# EthToRS485_V1_AUTO.net
KiCad netlist of a schematic drawn in EAGLE
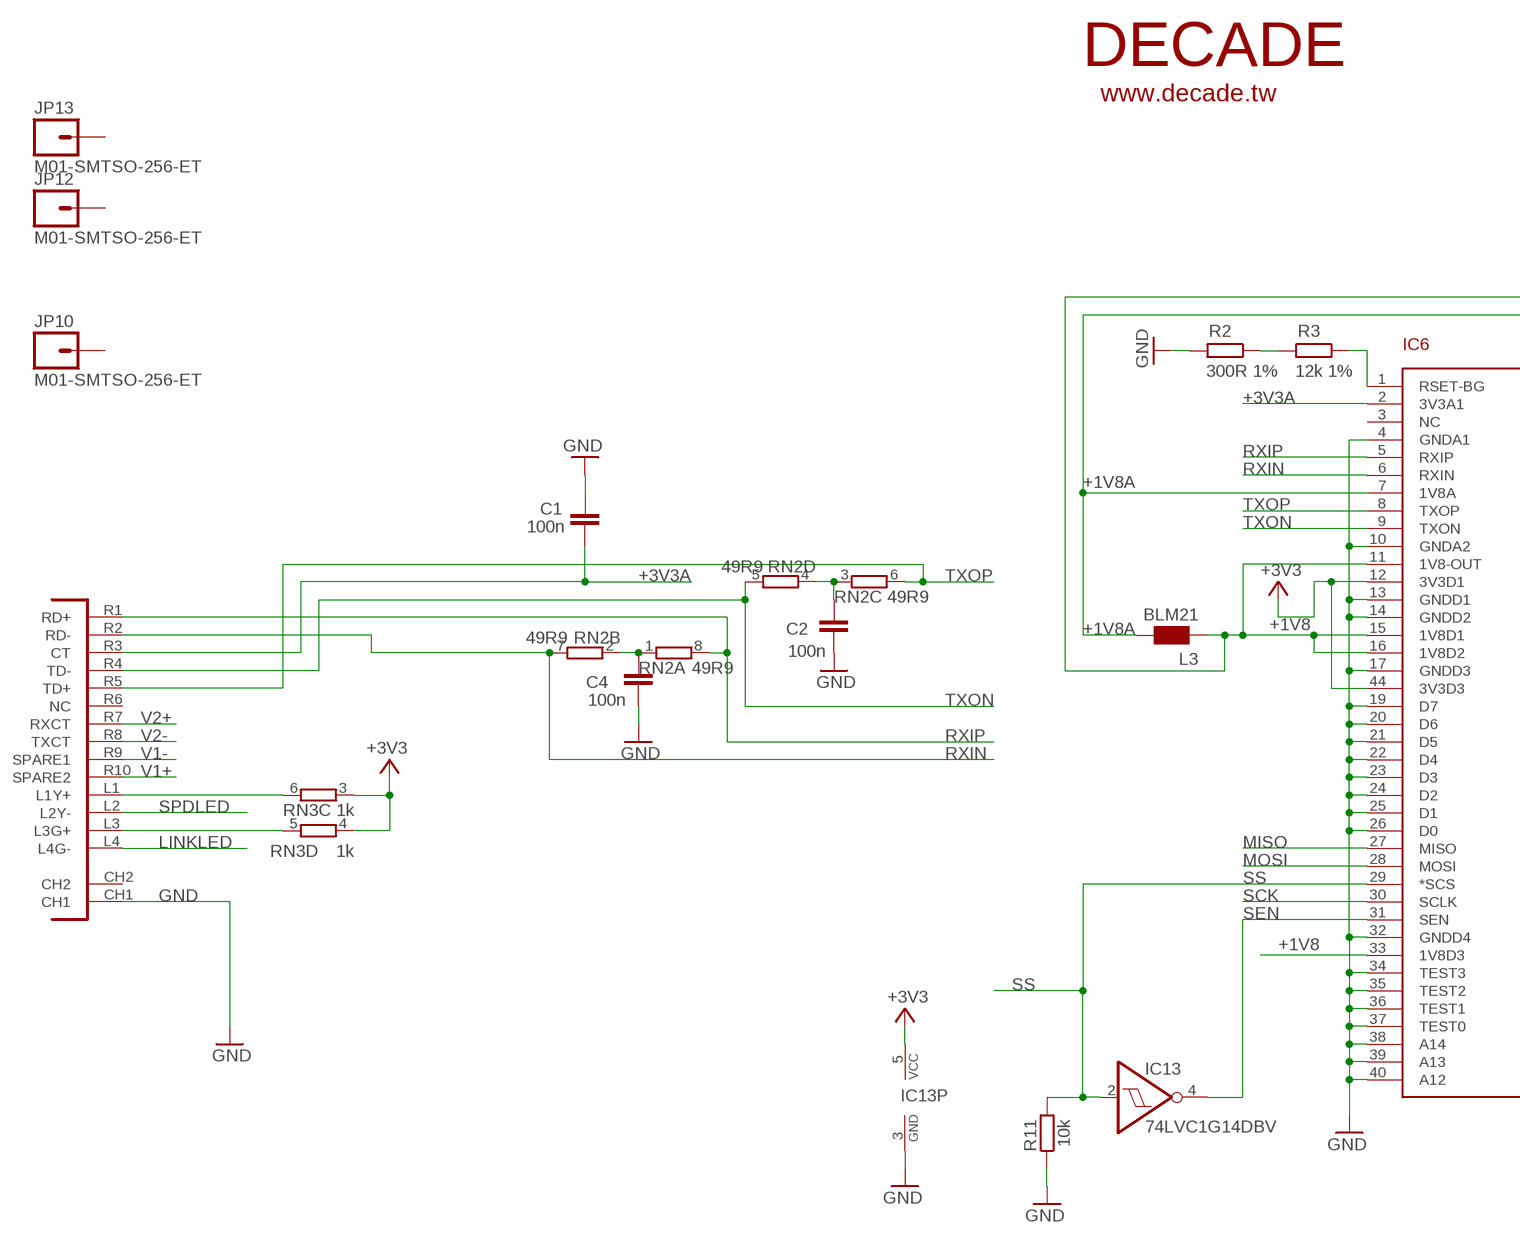
[diagram p0: schematic, sheet 1, part 1 of 3]
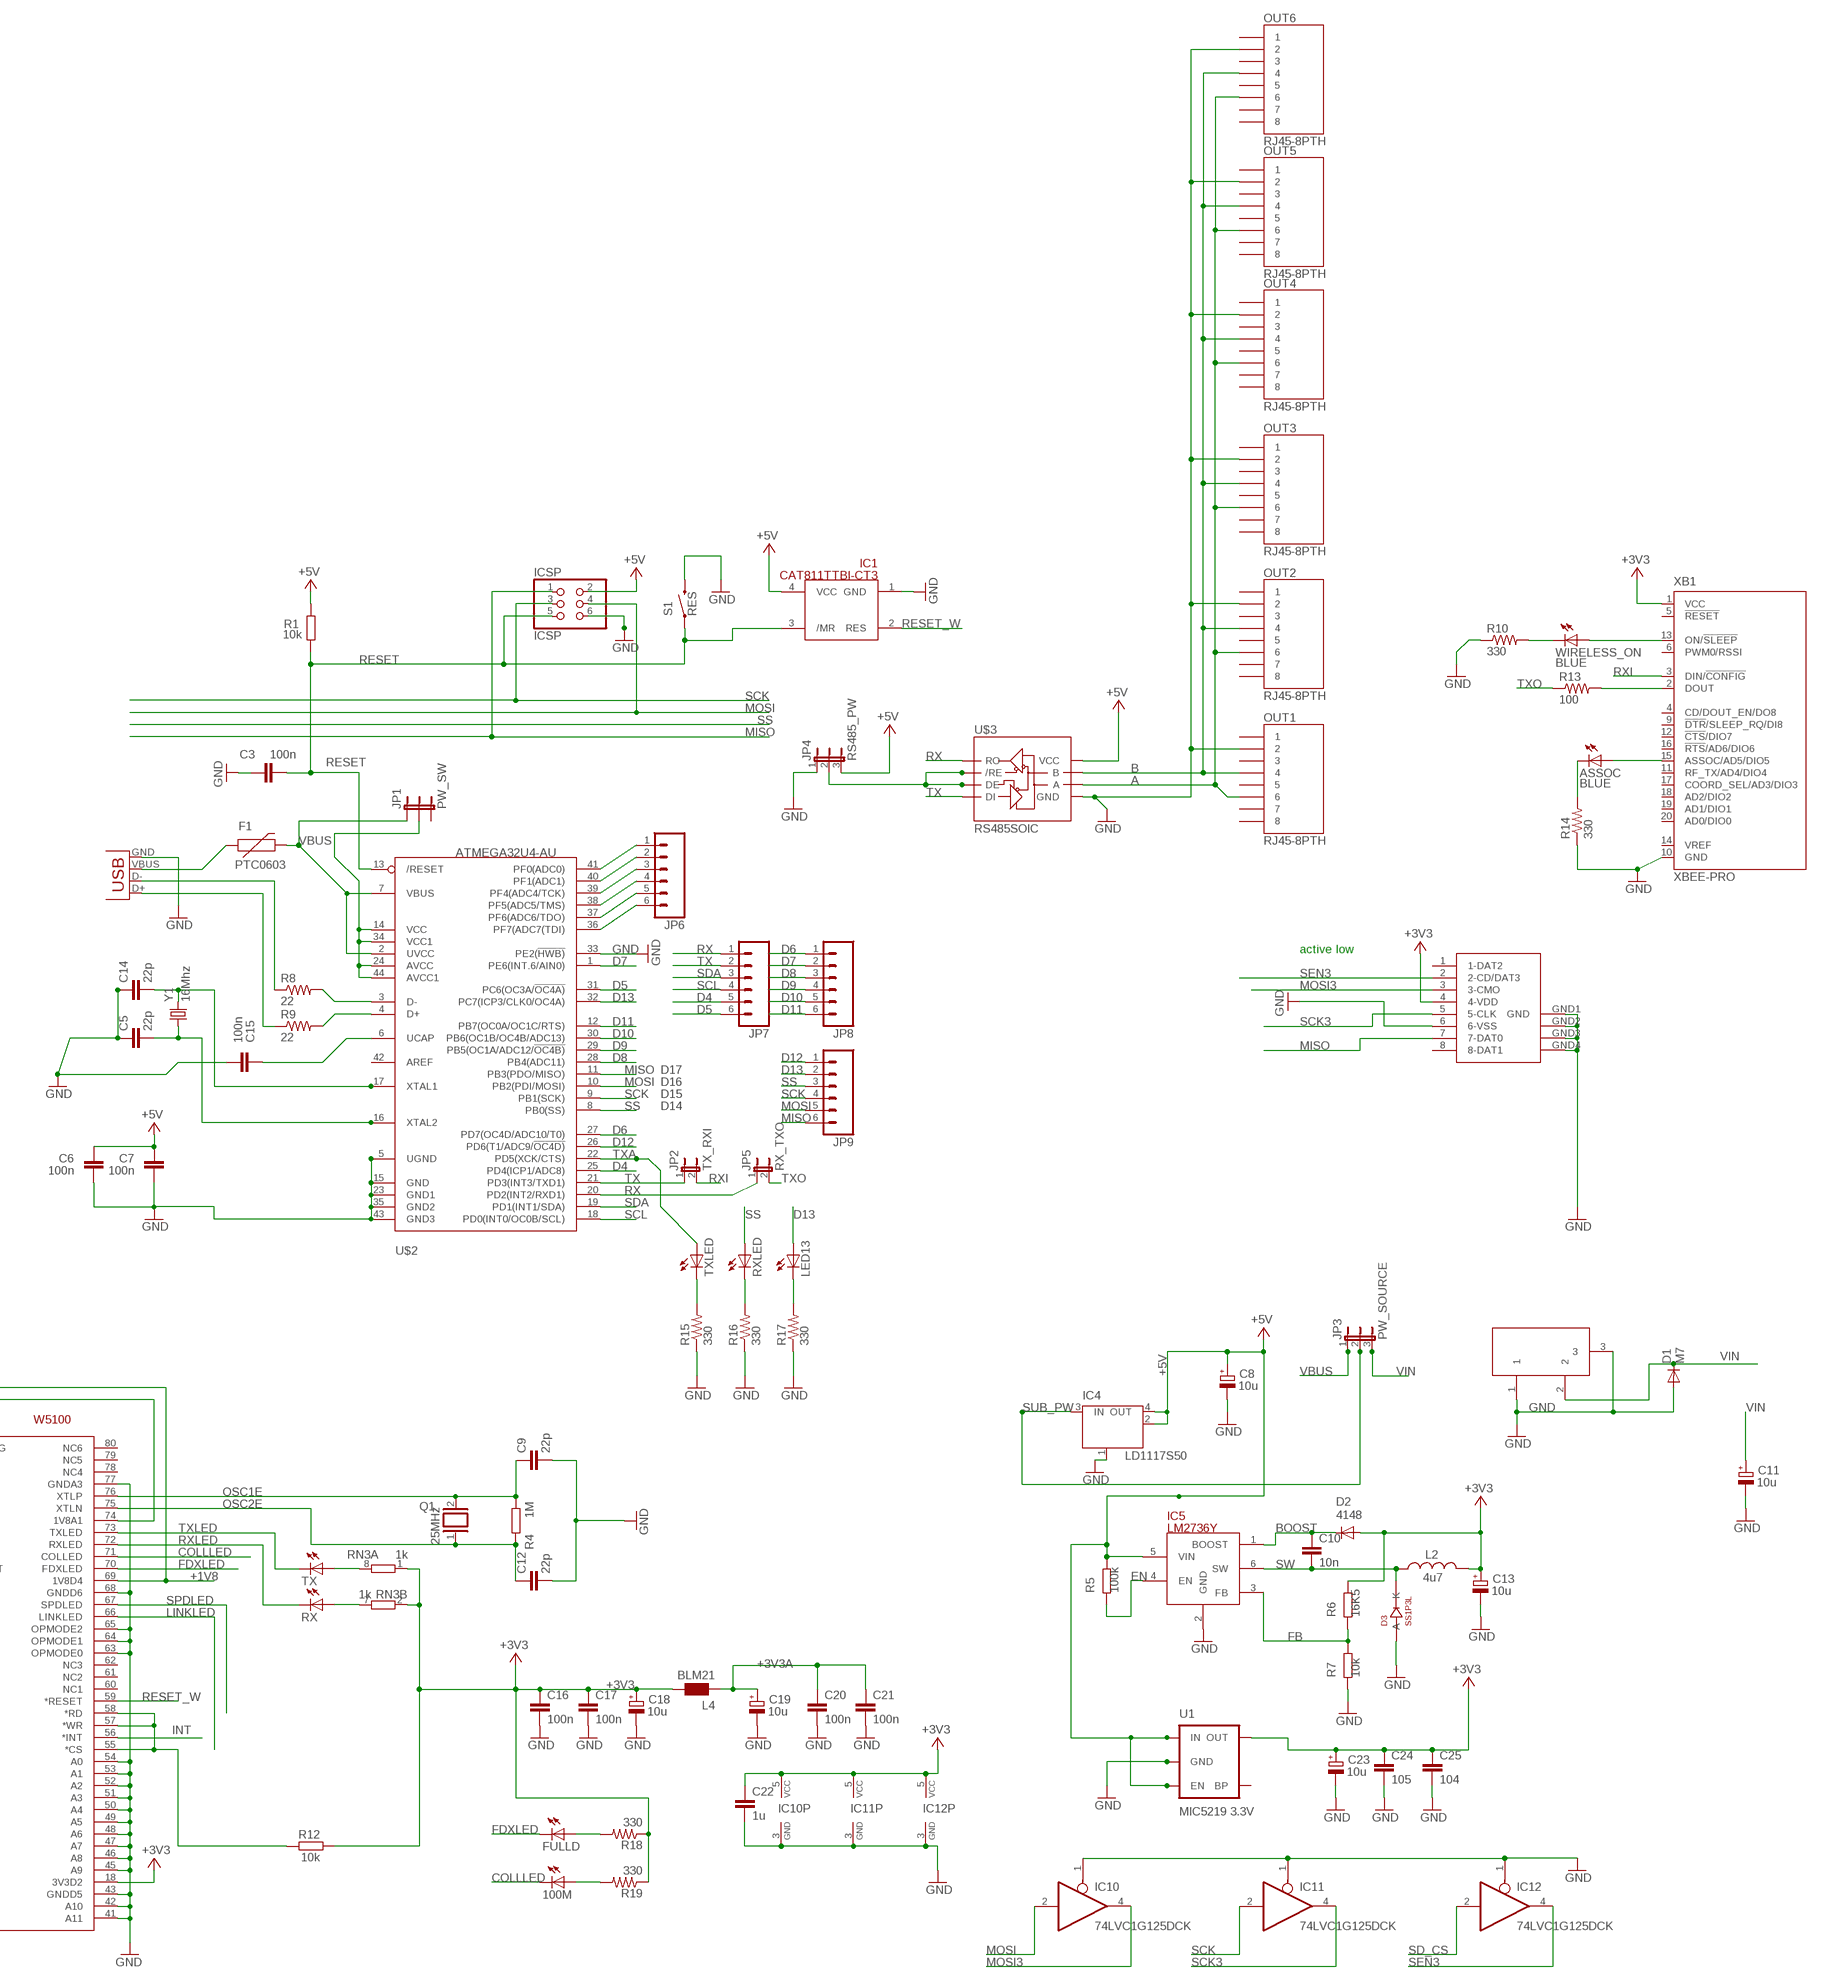
[diagram p1: schematic, sheet 1, part 2 of 3]
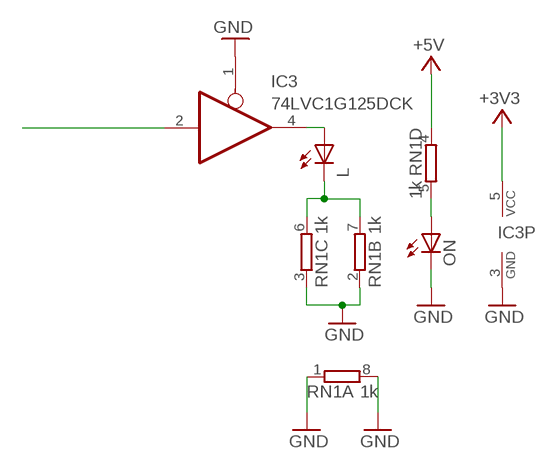
[diagram p2: schematic, sheet 1, part 3 of 3]

(export (version "E")
  (design (tool "Eeschema 10.0.6"))
  (components
    (comp (ref "100M")
      (value "LEDCHIPLED_0805")
      (footprint "eagle-import:CHIPLED_0805")
      (libsource (lib "eagle-import") (part "LEDCHIPLED_0805"))
    )
    (comp (ref "ASSOC")
      (value "BLUE")
      (footprint "eagle-import:CHIPLED_0805")
      (libsource (lib "eagle-import") (part "LEDCHIPLED_0805"))
    )
    (comp (ref "C1")
      (value "100n")
      (footprint "eagle-import:C0603-ROUND")
      (libsource (lib "eagle-import") (part "C-EUC0603"))
    )
    (comp (ref "C2")
      (value "100n")
      (footprint "eagle-import:C0603-ROUND")
      (libsource (lib "eagle-import") (part "C-EUC0603"))
    )
    (comp (ref "C3")
      (value "100n")
      (footprint "eagle-import:C0603-ROUND")
      (libsource (lib "eagle-import") (part "C-EUC0603"))
    )
    (comp (ref "C4")
      (value "100n")
      (footprint "eagle-import:C0603-ROUND")
      (libsource (lib "eagle-import") (part "C-EUC0603"))
    )
    (comp (ref "C5")
      (value "22p")
      (footprint "eagle-import:0805")
      (libsource (lib "eagle-import") (part "CAP0805"))
    )
    (comp (ref "C6")
      (value "100n")
      (footprint "eagle-import:C0603-ROUND")
      (libsource (lib "eagle-import") (part "C-EUC0603"))
    )
    (comp (ref "C7")
      (value "100n")
      (footprint "eagle-import:C0603-ROUND")
      (libsource (lib "eagle-import") (part "C-EUC0603"))
    )
    (comp (ref "C8")
      (value "10u")
      (footprint "eagle-import:SMC_B")
      (libsource (lib "eagle-import") (part "CPOL-EUSMCB"))
    )
    (comp (ref "C9")
      (value "22p")
      (footprint "eagle-import:C0603-ROUND")
      (libsource (lib "eagle-import") (part "C-EUC0603"))
    )
    (comp (ref "C10")
      (value "10n")
      (footprint "eagle-import:C0603-ROUND")
      (libsource (lib "eagle-import") (part "C-EUC0603"))
    )
    (comp (ref "C11")
      (value "10u")
      (footprint "eagle-import:SMC_B")
      (libsource (lib "eagle-import") (part "CPOL-EUSMCB"))
    )
    (comp (ref "C12")
      (value "22p")
      (footprint "eagle-import:C0603-ROUND")
      (libsource (lib "eagle-import") (part "C-EUC0603"))
    )
    (comp (ref "C13")
      (value "10u")
      (footprint "eagle-import:SMC_B")
      (libsource (lib "eagle-import") (part "CPOL-EUSMCB"))
    )
    (comp (ref "C14")
      (value "22p")
      (footprint "eagle-import:0805")
      (libsource (lib "eagle-import") (part "CAP0805"))
    )
    (comp (ref "C15")
      (value "100n")
      (footprint "eagle-import:C0603-ROUND")
      (libsource (lib "eagle-import") (part "C-EUC0603"))
    )
    (comp (ref "C16")
      (value "100n")
      (footprint "eagle-import:C0603-ROUND")
      (libsource (lib "eagle-import") (part "C-EUC0603"))
    )
    (comp (ref "C17")
      (value "100n")
      (footprint "eagle-import:C0603-ROUND")
      (libsource (lib "eagle-import") (part "C-EUC0603"))
    )
    (comp (ref "C18")
      (value "10u")
      (footprint "eagle-import:SMC_B")
      (libsource (lib "eagle-import") (part "CPOL-EUSMCB"))
    )
    (comp (ref "C19")
      (value "10u")
      (footprint "eagle-import:SMC_B")
      (libsource (lib "eagle-import") (part "CPOL-EUSMCB"))
    )
    (comp (ref "C20")
      (value "100n")
      (footprint "eagle-import:C0603-ROUND")
      (libsource (lib "eagle-import") (part "C-EUC0603"))
    )
    (comp (ref "C21")
      (value "100n")
      (footprint "eagle-import:C0603-ROUND")
      (libsource (lib "eagle-import") (part "C-EUC0603"))
    )
    (comp (ref "C22")
      (value "1u")
      (footprint "eagle-import:C0603-ROUND")
      (libsource (lib "eagle-import") (part "C-EUC0603"))
    )
    (comp (ref "C23")
      (value "10u")
      (footprint "eagle-import:SMC_B")
      (libsource (lib "eagle-import") (part "CPOL-EUSMCB"))
    )
    (comp (ref "C24")
      (value "105")
      (footprint "eagle-import:C0603-ROUND")
      (libsource (lib "eagle-import") (part "C-EUC0603"))
    )
    (comp (ref "C25")
      (value "104")
      (footprint "eagle-import:C0603-ROUND")
      (libsource (lib "eagle-import") (part "C-EUC0603"))
    )
    (comp (ref "D1")
      (value "M7")
      (footprint "eagle-import:SMB")
      (libsource (lib "eagle-import") (part "DIODE-SMB"))
    )
    (comp (ref "D2")
      (value "4148")
      (footprint "eagle-import:MINIMELF")
      (libsource (lib "eagle-import") (part "DIODE-MINIMELF"))
    )
    (comp (ref "D3")
      (value "SS1P3L")
      (footprint "eagle-import:DO220AAL")
      (libsource (lib "eagle-import") (part "SS1P3L"))
    )
    (comp (ref "F1")
      (value "PTC0603")
      (footprint "eagle-import:0603")
      (libsource (lib "eagle-import") (part "PTC0603"))
    )
    (comp (ref "FULLD")
      (value "LEDCHIPLED_0805")
      (footprint "eagle-import:CHIPLED_0805")
      (libsource (lib "eagle-import") (part "LEDCHIPLED_0805"))
    )
    (comp (ref "IC1")
      (value "CAT811TTBI-CT3")
      (footprint "eagle-import:SOT143")
      (libsource (lib "eagle-import") (part "STM812"))
    )
    (comp (ref "IC3")
      (value "74LVC1G125DCK")
      (footprint "eagle-import:SC70-5")
      (libsource (lib "eagle-import") (part "741G125DCKLVC"))
    )
    (comp (ref "IC4")
      (value "LD1117S50")
      (footprint "eagle-import:SOT223")
      (libsource (lib "eagle-import") (part "MC33269ST-3.3T3"))
    )
    (comp (ref "IC5")
      (value "LM2736Y")
      (footprint "eagle-import:SOT23-6")
      (libsource (lib "eagle-import") (part "LM2736Y"))
    )
    (comp (ref "IC6")
      (value "W5100")
      (footprint "eagle-import:SQFP-S-10X10-80")
      (libsource (lib "eagle-import") (part "W5100"))
    )
    (comp (ref "IC10")
      (value "74LVC1G125DCK")
      (footprint "eagle-import:SC70-5")
      (libsource (lib "eagle-import") (part "741G125DCKLVC"))
    )
    (comp (ref "IC11")
      (value "74LVC1G125DCK")
      (footprint "eagle-import:SC70-5")
      (libsource (lib "eagle-import") (part "741G125DCKLVC"))
    )
    (comp (ref "IC12")
      (value "74LVC1G125DCK")
      (footprint "eagle-import:SC70-5")
      (libsource (lib "eagle-import") (part "741G125DCKLVC"))
    )
    (comp (ref "IC13")
      (value "74LVC1G14DBV")
      (footprint "eagle-import:SOT23-5")
      (libsource (lib "eagle-import") (part "741G14DBVLVC"))
    )
    (comp (ref "ICSP")
      (value "ICSP")
      (footprint "eagle-import:2X03")
      (libsource (lib "eagle-import") (part "PINHD-2X3"))
    )
    (comp (ref "JP1")
      (value "PW_SW")
      (footprint "eagle-import:SJ_3")
      (libsource (lib "eagle-import") (part "JUMPER-3SMD"))
    )
    (comp (ref "JP2")
      (value "TX_RXI")
      (footprint "eagle-import:JP1")
      (libsource (lib "eagle-import") (part "JP1E"))
    )
    (comp (ref "JP3")
      (value "PW_SOURCE")
      (footprint "eagle-import:JP2")
      (libsource (lib "eagle-import") (part "JP2E"))
    )
    (comp (ref "JP4")
      (value "RS485_PW")
      (footprint "eagle-import:JP2")
      (libsource (lib "eagle-import") (part "JP2E"))
    )
    (comp (ref "JP5")
      (value "RX_TXO")
      (footprint "eagle-import:JP1")
      (libsource (lib "eagle-import") (part "JP1E"))
    )
    (comp (ref "JP6")
      (value "M06SIP")
      (footprint "eagle-import:1X06")
      (libsource (lib "eagle-import") (part "M06SIP"))
    )
    (comp (ref "JP7")
      (value "M06SIP")
      (footprint "eagle-import:1X06")
      (libsource (lib "eagle-import") (part "M06SIP"))
    )
    (comp (ref "JP8")
      (value "M06SIP")
      (footprint "eagle-import:1X06")
      (libsource (lib "eagle-import") (part "M06SIP"))
    )
    (comp (ref "JP9")
      (value "M06SIP")
      (footprint "eagle-import:1X06")
      (libsource (lib "eagle-import") (part "M06SIP"))
    )
    (comp (ref "JP10")
      (value "M01-SMTSO-256-ET")
      (footprint "eagle-import:SMTSO-256-ET")
      (libsource (lib "eagle-import") (part "M01-SMTSO-256-ET"))
    )
    (comp (ref "JP12")
      (value "M01-SMTSO-256-ET")
      (footprint "eagle-import:SMTSO-256-ET")
      (libsource (lib "eagle-import") (part "M01-SMTSO-256-ET"))
    )
    (comp (ref "JP13")
      (value "M01-SMTSO-256-ET")
      (footprint "eagle-import:SMTSO-256-ET")
      (libsource (lib "eagle-import") (part "M01-SMTSO-256-ET"))
    )
    (comp (ref "L")
      (value "LEDCHIPLED_0805")
      (footprint "eagle-import:CHIPLED_0805")
      (libsource (lib "eagle-import") (part "LEDCHIPLED_0805"))
    )
    (comp (ref "L2")
      (value "4u7")
      (footprint "eagle-import:SRR0604")
      (libsource (lib "eagle-import") (part "L-USSRR0604"))
    )
    (comp (ref "L3")
      (value "BLM21")
      (footprint "eagle-import:0805")
      (libsource (lib "eagle-import") (part "WE-CBF_0805"))
    )
    (comp (ref "L4")
      (value "BLM21")
      (footprint "eagle-import:0805")
      (libsource (lib "eagle-import") (part "WE-CBF_0805"))
    )
    (comp (ref "LED13")
      (value "LEDCHIPLED_0805")
      (footprint "eagle-import:CHIPLED_0805")
      (libsource (lib "eagle-import") (part "LEDCHIPLED_0805"))
    )
    (comp (ref "ON")
      (value "LEDCHIPLED_0805")
      (footprint "eagle-import:CHIPLED_0805")
      (libsource (lib "eagle-import") (part "LEDCHIPLED_0805"))
    )
    (comp (ref "OUT1")
      (value "RJ45-8PTH")
      (footprint "eagle-import:RJ45-8")
      (libsource (lib "eagle-import") (part "RJ45-8PTH"))
    )
    (comp (ref "OUT2")
      (value "RJ45-8PTH")
      (footprint "eagle-import:RJ45-8")
      (libsource (lib "eagle-import") (part "RJ45-8PTH"))
    )
    (comp (ref "OUT3")
      (value "RJ45-8PTH")
      (footprint "eagle-import:RJ45-8")
      (libsource (lib "eagle-import") (part "RJ45-8PTH"))
    )
    (comp (ref "OUT4")
      (value "RJ45-8PTH")
      (footprint "eagle-import:RJ45-8")
      (libsource (lib "eagle-import") (part "RJ45-8PTH"))
    )
    (comp (ref "OUT5")
      (value "RJ45-8PTH")
      (footprint "eagle-import:RJ45-8")
      (libsource (lib "eagle-import") (part "RJ45-8PTH"))
    )
    (comp (ref "OUT6")
      (value "RJ45-8PTH")
      (footprint "eagle-import:RJ45-8")
      (libsource (lib "eagle-import") (part "RJ45-8PTH"))
    )
    (comp (ref "Q1")
      (value "25MHz")
      (footprint "eagle-import:QS")
      (libsource (lib "eagle-import") (part "XTAL/S"))
    )
    (comp (ref "R1")
      (value "10k")
      (footprint "eagle-import:R0603-ROUND")
      (libsource (lib "eagle-import") (part "R-EU_0603-RND"))
    )
    (comp (ref "R2")
      (value "300R 1%")
      (footprint "eagle-import:R0603-ROUND")
      (libsource (lib "eagle-import") (part "R-EU_0603-RND"))
    )
    (comp (ref "R3")
      (value "12k 1%")
      (footprint "eagle-import:R0603-ROUND")
      (libsource (lib "eagle-import") (part "R-EU_0603-RND"))
    )
    (comp (ref "R4")
      (value "1M")
      (footprint "eagle-import:R0603-ROUND")
      (libsource (lib "eagle-import") (part "R-EU_0603-RND"))
    )
    (comp (ref "R5")
      (value "100k")
      (footprint "eagle-import:R0603-ROUND")
      (libsource (lib "eagle-import") (part "R-EU_0603-RND"))
    )
    (comp (ref "R6")
      (value "16K5")
      (footprint "eagle-import:R0603-ROUND")
      (libsource (lib "eagle-import") (part "R-EU_0603-RND"))
    )
    (comp (ref "R7")
      (value "10k")
      (footprint "eagle-import:R0603-ROUND")
      (libsource (lib "eagle-import") (part "R-EU_0603-RND"))
    )
    (comp (ref "R8")
      (value "22")
      (footprint "eagle-import:0805")
      (libsource (lib "eagle-import") (part "RESISTOR0805-RES"))
    )
    (comp (ref "R9")
      (value "22")
      (footprint "eagle-import:0805")
      (libsource (lib "eagle-import") (part "RESISTOR0805-RES"))
    )
    (comp (ref "R10")
      (value "330")
      (footprint "eagle-import:0805")
      (libsource (lib "eagle-import") (part "RESISTOR0805-RES"))
    )
    (comp (ref "R11")
      (value "10k")
      (footprint "eagle-import:R0603-ROUND")
      (libsource (lib "eagle-import") (part "R-EU_0603-RND"))
    )
    (comp (ref "R12")
      (value "10k")
      (footprint "eagle-import:R0603-ROUND")
      (libsource (lib "eagle-import") (part "R-EU_R0603"))
    )
    (comp (ref "R13")
      (value "100")
      (footprint "eagle-import:0805")
      (libsource (lib "eagle-import") (part "RESISTOR0805-RES"))
    )
    (comp (ref "R14")
      (value "330")
      (footprint "eagle-import:0805")
      (libsource (lib "eagle-import") (part "RESISTOR0805-RES"))
    )
    (comp (ref "R15")
      (value "330")
      (footprint "eagle-import:0805")
      (libsource (lib "eagle-import") (part "RESISTOR0805-RES"))
    )
    (comp (ref "R16")
      (value "330")
      (footprint "eagle-import:0805")
      (libsource (lib "eagle-import") (part "RESISTOR0805-RES"))
    )
    (comp (ref "R17")
      (value "330")
      (footprint "eagle-import:0805")
      (libsource (lib "eagle-import") (part "RESISTOR0805-RES"))
    )
    (comp (ref "R18")
      (value "330")
      (footprint "eagle-import:0805")
      (libsource (lib "eagle-import") (part "RESISTOR0805-RES"))
    )
    (comp (ref "R19")
      (value "330")
      (footprint "eagle-import:0805")
      (libsource (lib "eagle-import") (part "RESISTOR0805-RES"))
    )
    (comp (ref "RN1")
      (value "1k")
      (footprint "eagle-import:CAY16")
      (libsource (lib "eagle-import") (part "4R-NCAY16"))
    )
    (comp (ref "RN2")
      (value "49R9")
      (footprint "eagle-import:CAY16")
      (libsource (lib "eagle-import") (part "4R-NCAY16"))
    )
    (comp (ref "RN3")
      (value "1k")
      (footprint "eagle-import:CAY16")
      (libsource (lib "eagle-import") (part "4R-NCAY16"))
    )
    (comp (ref "RX")
      (value "LEDCHIPLED_0805")
      (footprint "eagle-import:CHIPLED_0805")
      (libsource (lib "eagle-import") (part "LEDCHIPLED_0805"))
    )
    (comp (ref "RXLED")
      (value "LEDCHIPLED_0805")
      (footprint "eagle-import:CHIPLED_0805")
      (libsource (lib "eagle-import") (part "LEDCHIPLED_0805"))
    )
    (comp (ref "S1")
      (value "RES")
      (footprint "eagle-import:TACTILE-SWITCH-1101NE")
      (libsource (lib "eagle-import") (part "SWITCH-MOMENTARY-2-SMD-1101NE"))
    )
    (comp (ref "TX")
      (value "LEDCHIPLED_0805")
      (footprint "eagle-import:CHIPLED_0805")
      (libsource (lib "eagle-import") (part "LEDCHIPLED_0805"))
    )
    (comp (ref "TXLED")
      (value "LEDCHIPLED_0805")
      (footprint "eagle-import:CHIPLED_0805")
      (libsource (lib "eagle-import") (part "LEDCHIPLED_0805"))
    )
    (comp (ref "U$1")
      (value "POE-RJ45")
      (footprint "eagle-import:POE-RJ45")
      (libsource (lib "eagle-import") (part "POE-RJ45"))
    )
    (comp (ref "U$2")
      (value "ATMEGA32U4-AU")
      (footprint "eagle-import:TQFP44")
      (libsource (lib "eagle-import") (part "ATMEGA32U4-AU"))
    )
    (comp (ref "U$3")
      (value "RS485SOIC")
      (footprint "eagle-import:SO08")
      (libsource (lib "eagle-import") (part "RS485SOIC"))
    )
    (comp (ref "U$4")
      (value "DECADE-LOGO-SMALL")
      (footprint "eagle-import:DECADE-LOGO-SMALL")
      (libsource (lib "eagle-import") (part "DECADE-LOGO-SMALL"))
    )
    (comp (ref "U1")
      (value "MIC5219 3.3V")
      (footprint "eagle-import:SOT23-5")
      (libsource (lib "eagle-import") (part "V_REG_MIC52193.3V"))
    )
    (comp (ref "WIRELESS_ON")
      (value "BLUE")
      (footprint "eagle-import:CHIPLED_0805")
      (libsource (lib "eagle-import") (part "LEDCHIPLED_0805"))
    )
    (comp (ref "X1")
      (value "DC21MMX")
      (footprint "eagle-import:DC-21MM")
      (libsource (lib "eagle-import") (part "DC21MMX"))
    )
    (comp (ref "X2")
      (value "SDCARD-15TW-8821")
      (footprint "eagle-import:SDCARD-15TW-8821")
      (libsource (lib "eagle-import") (part "SDCARD-15TW-8821"))
    )
    (comp (ref "X3")
      (value "USBOLD")
      (footprint "eagle-import:USB-MINIB-OLD")
      (libsource (lib "eagle-import") (part "USBOLD"))
    )
    (comp (ref "XB1")
      (value "XBEE-PRO")
      (footprint "eagle-import:XBEE-PRO")
      (fields (field (name "MPN") "XBP24-AWI-001"))
      (libsource (lib "eagle-import") (part "XBEE-PRO"))
    )
    (comp (ref "Y1")
      (value "16Mhz")
      (footprint "eagle-import:CRYSTAL-SMD-5X3")
      (libsource (lib "eagle-import") (part "CRYSTAL5X3"))
    )
  )
  (nets
    (net (code "1") (name "+3V3") (class "Default")
      (node (ref "C13") (pin "+") (pinfunction "+_+") (pintype "passive"))
      (node (ref "C16") (pin "1") (pinfunction "1_1") (pintype "passive"))
      (node (ref "C17") (pin "1") (pinfunction "1_1") (pintype "passive"))
      (node (ref "C18") (pin "+") (pinfunction "+_+") (pintype "passive"))
      (node (ref "C22") (pin "1") (pinfunction "1_1") (pintype "passive"))
      (node (ref "C23") (pin "+") (pinfunction "+_+") (pintype "passive"))
      (node (ref "C24") (pin "1") (pinfunction "1_1") (pintype "passive"))
      (node (ref "C25") (pin "1") (pinfunction "1_1") (pintype "passive"))
      (node (ref "D2") (pin "A") (pinfunction "A_A") (pintype "passive"))
      (node (ref "IC10") (pin "5") (pinfunction "VCC_5") (pintype "power_in"))
      (node (ref "IC11") (pin "5") (pinfunction "VCC_5") (pintype "power_in"))
      (node (ref "IC12") (pin "5") (pinfunction "VCC_5") (pintype "power_in"))
      (node (ref "IC13") (pin "5") (pinfunction "VCC_5") (pintype "power_in"))
      (node (ref "IC3") (pin "5") (pinfunction "VCC_5") (pintype "power_in"))
      (node (ref "IC6") (pin "12") (pinfunction "3V3D1_12") (pintype "power_in"))
      (node (ref "IC6") (pin "18") (pinfunction "3V3D2_18") (pintype "power_in"))
      (node (ref "IC6") (pin "44") (pinfunction "3V3D3_44") (pintype "power_in"))
      (node (ref "L2") (pin "P$2") (pinfunction "2_P$2") (pintype "passive"))
      (node (ref "L4") (pin "2") (pinfunction "2_2") (pintype "passive"))
      (node (ref "R12") (pin "2") (pinfunction "2_2") (pintype "passive"))
      (node (ref "R18") (pin "1") (pinfunction "1_1") (pintype "passive"))
      (node (ref "R19") (pin "1") (pinfunction "1_1") (pintype "passive"))
      (node (ref "R6") (pin "1") (pinfunction "1_1") (pintype "passive"))
      (node (ref "RN3") (pin "1") (pinfunction "1_1") (pintype "passive"))
      (node (ref "RN3") (pin "2") (pinfunction "1_2") (pintype "passive"))
      (node (ref "RN3") (pin "3") (pinfunction "1_3") (pintype "passive"))
      (node (ref "RN3") (pin "4") (pinfunction "1_4") (pintype "passive"))
      (node (ref "U1") (pin "5") (pinfunction "OUT_5") (pintype "passive"))
      (node (ref "X2") (pin "4") (pinfunction "4-VDD_4") (pintype "bidirectional"))
      (node (ref "XB1") (pin "1") (pinfunction "VCC_1") (pintype "power_in"))
    )
    (net (code "2") (name "+5V") (class "Default")
      (node (ref "C6") (pin "1") (pinfunction "1_1") (pintype "passive"))
      (node (ref "C7") (pin "1") (pinfunction "1_1") (pintype "passive"))
      (node (ref "C8") (pin "+") (pinfunction "+_+") (pintype "passive"))
      (node (ref "IC1") (pin "4") (pinfunction "VCC_4") (pintype "power_in"))
      (node (ref "IC4") (pin "2") (pinfunction "OUT_2") (pintype "passive"))
      (node (ref "IC4") (pin "4") (pinfunction "OUT_4") (pintype "passive"))
      (node (ref "IC5") (pin "5") (pinfunction "VIN_5") (pintype "input"))
      (node (ref "ICSP") (pin "2") (pinfunction "2_2") (pintype "passive"))
      (node (ref "JP4") (pin "3") (pinfunction "3_3") (pintype "passive"))
      (node (ref "R1") (pin "2") (pinfunction "2_2") (pintype "passive"))
      (node (ref "R5") (pin "1") (pinfunction "1_1") (pintype "passive"))
      (node (ref "RN1") (pin "4") (pinfunction "1_4") (pintype "passive"))
      (node (ref "U$3") (pin "8") (pinfunction "VCC_8") (pintype "bidirectional"))
      (node (ref "U1") (pin "1") (pinfunction "IN_1") (pintype "input"))
      (node (ref "U1") (pin "3") (pinfunction "EN_3") (pintype "input"))
    )
    (net (code "3") (name "/+1V8") (class "Default")
      (node (ref "IC6") (pin "11") (pinfunction "1V8-OUT_11") (pintype "power_in"))
      (node (ref "IC6") (pin "15") (pinfunction "1V8D1_15") (pintype "power_in"))
      (node (ref "IC6") (pin "16") (pinfunction "1V8D2_16") (pintype "power_in"))
      (node (ref "IC6") (pin "33") (pinfunction "1V8D3_33") (pintype "power_in"))
      (node (ref "IC6") (pin "69") (pinfunction "1V8D4_69") (pintype "power_in"))
      (node (ref "L3") (pin "1") (pinfunction "1_1") (pintype "passive"))
    )
    (net (code "4") (name "/+1V8A") (class "Default")
      (node (ref "IC6") (pin "7") (pinfunction "1V8A_7") (pintype "power_in"))
      (node (ref "IC6") (pin "74") (pinfunction "1V8A1_74") (pintype "power_in"))
      (node (ref "L3") (pin "2") (pinfunction "2_2") (pintype "passive"))
    )
    (net (code "5") (name "/+3V3A") (class "Default")
      (node (ref "C1") (pin "1") (pinfunction "1_1") (pintype "passive"))
      (node (ref "C19") (pin "+") (pinfunction "+_+") (pintype "passive"))
      (node (ref "C20") (pin "1") (pinfunction "1_1") (pintype "passive"))
      (node (ref "C21") (pin "1") (pinfunction "1_1") (pintype "passive"))
      (node (ref "IC6") (pin "2") (pinfunction "3V3A1_2") (pintype "power_in"))
      (node (ref "L4") (pin "1") (pinfunction "1_1") (pintype "passive"))
      (node (ref "U$1") (pin "R3") (pinfunction "CT_R3") (pintype "bidirectional"))
    )
    (net (code "6") (name "/A") (class "Default")
      (node (ref "OUT1") (pin "6") (pinfunction "6_6") (pintype "bidirectional"))
      (node (ref "OUT2") (pin "6") (pinfunction "6_6") (pintype "bidirectional"))
      (node (ref "OUT3") (pin "6") (pinfunction "6_6") (pintype "bidirectional"))
      (node (ref "OUT4") (pin "6") (pinfunction "6_6") (pintype "bidirectional"))
      (node (ref "OUT5") (pin "6") (pinfunction "6_6") (pintype "bidirectional"))
      (node (ref "OUT6") (pin "6") (pinfunction "6_6") (pintype "bidirectional"))
      (node (ref "U$3") (pin "6") (pinfunction "A_6") (pintype "bidirectional"))
    )
    (net (code "7") (name "/B") (class "Default")
      (node (ref "OUT1") (pin "4") (pinfunction "4_4") (pintype "bidirectional"))
      (node (ref "OUT2") (pin "4") (pinfunction "4_4") (pintype "bidirectional"))
      (node (ref "OUT3") (pin "4") (pinfunction "4_4") (pintype "bidirectional"))
      (node (ref "OUT4") (pin "4") (pinfunction "4_4") (pintype "bidirectional"))
      (node (ref "OUT5") (pin "4") (pinfunction "4_4") (pintype "bidirectional"))
      (node (ref "OUT6") (pin "4") (pinfunction "4_4") (pintype "bidirectional"))
      (node (ref "U$3") (pin "7") (pinfunction "B_7") (pintype "bidirectional"))
    )
    (net (code "8") (name "/BOOST") (class "Default")
      (node (ref "C10") (pin "1") (pinfunction "1_1") (pintype "passive"))
      (node (ref "D2") (pin "C") (pinfunction "C_C") (pintype "passive"))
      (node (ref "IC5") (pin "1") (pinfunction "BOOST_1") (pintype "input"))
    )
    (net (code "9") (name "/COLLLED") (class "Default")
      (node (ref "100M") (pin "C") (pinfunction "C_C") (pintype "passive"))
      (node (ref "IC6") (pin "71") (pinfunction "COLLED_71") (pintype "output"))
    )
    (net (code "10") (name "/D4") (class "Default")
      (node (ref "JP7") (pin "5") (pinfunction "5_5") (pintype "passive"))
      (node (ref "U$2") (pin "25") (pinfunction "PD4(ICP1/ADC8)_25") (pintype "bidirectional"))
    )
    (net (code "11") (name "/D5") (class "Default")
      (node (ref "JP7") (pin "6") (pinfunction "6_6") (pintype "passive"))
      (node (ref "U$2") (pin "31") (pinfunction "PC6(OC3A/~{OC4A})_31") (pintype "bidirectional"))
    )
    (net (code "12") (name "/D6") (class "Default")
      (node (ref "JP8") (pin "1") (pinfunction "1_1") (pintype "passive"))
      (node (ref "U$2") (pin "27") (pinfunction "PD7(OC4D/ADC10/T0)_27") (pintype "bidirectional"))
    )
    (net (code "13") (name "/D7") (class "Default")
      (node (ref "JP8") (pin "2") (pinfunction "2_2") (pintype "passive"))
      (node (ref "U$2") (pin "1") (pinfunction "PE6(INT.6/AIN0)_1") (pintype "bidirectional"))
    )
    (net (code "14") (name "/D8") (class "Default")
      (node (ref "JP8") (pin "3") (pinfunction "3_3") (pintype "passive"))
      (node (ref "U$2") (pin "28") (pinfunction "PB4(ADC11)_28") (pintype "bidirectional"))
    )
    (net (code "15") (name "/D9") (class "Default")
      (node (ref "JP8") (pin "4") (pinfunction "4_4") (pintype "passive"))
      (node (ref "U$2") (pin "29") (pinfunction "PB5(OC1A/ADC12/~{OC4B})_29") (pintype "bidirectional"))
    )
    (net (code "16") (name "/D10") (class "Default")
      (node (ref "JP8") (pin "5") (pinfunction "5_5") (pintype "passive"))
      (node (ref "U$2") (pin "30") (pinfunction "PB6(OC1B/OC4B/ADC13)_30") (pintype "bidirectional"))
    )
    (net (code "17") (name "/D11") (class "Default")
      (node (ref "JP8") (pin "6") (pinfunction "6_6") (pintype "passive"))
      (node (ref "U$2") (pin "12") (pinfunction "PB7(OC0A/OC1C/RTS)_12") (pintype "bidirectional"))
    )
    (net (code "18") (name "/D12") (class "Default")
      (node (ref "JP9") (pin "1") (pinfunction "1_1") (pintype "passive"))
      (node (ref "U$2") (pin "26") (pinfunction "PD6(T1/ADC9/~{OC4D})_26") (pintype "bidirectional"))
    )
    (net (code "19") (name "/D13") (class "Default")
      (node (ref "JP9") (pin "2") (pinfunction "2_2") (pintype "passive"))
      (node (ref "LED13") (pin "A") (pinfunction "A_A") (pintype "passive"))
      (node (ref "U$2") (pin "32") (pinfunction "PC7(ICP3/CLK0/OC4A)_32") (pintype "bidirectional"))
    )
    (net (code "20") (name "/EN") (class "Default")
      (node (ref "IC5") (pin "4") (pinfunction "EN_4") (pintype "input"))
      (node (ref "R5") (pin "2") (pinfunction "2_2") (pintype "passive"))
    )
    (net (code "21") (name "/FB") (class "Default")
      (node (ref "IC5") (pin "3") (pinfunction "FB_3") (pintype "input"))
      (node (ref "R6") (pin "2") (pinfunction "2_2") (pintype "passive"))
      (node (ref "R7") (pin "1") (pinfunction "1_1") (pintype "passive"))
    )
    (net (code "22") (name "/FDXLED") (class "Default")
      (node (ref "FULLD") (pin "C") (pinfunction "C_C") (pintype "passive"))
      (node (ref "IC6") (pin "70") (pinfunction "FDXLED_70") (pintype "output"))
    )
    (net (code "23") (name "/INT") (class "Default")
      (node (ref "IC6") (pin "56") (pinfunction "*INT_56") (pintype "input"))
    )
    (net (code "24") (name "/LINKLED") (class "Default")
      (node (ref "IC6") (pin "66") (pinfunction "LINKLED_66") (pintype "output"))
      (node (ref "U$1") (pin "L4") (pinfunction "L4G-_L4") (pintype "bidirectional"))
    )
    (net (code "25") (name "/MISO") (class "Default")
      (node (ref "IC6") (pin "27") (pinfunction "MISO_27") (pintype "input"))
      (node (ref "ICSP") (pin "1") (pinfunction "1_1") (pintype "passive"))
      (node (ref "JP9") (pin "6") (pinfunction "6_6") (pintype "passive"))
      (node (ref "U$2") (pin "11") (pinfunction "PB3(PDO/MISO)_11") (pintype "bidirectional"))
      (node (ref "X2") (pin "7") (pinfunction "7-DAT0_7") (pintype "bidirectional"))
    )
    (net (code "26") (name "/MOSI") (class "Default")
      (node (ref "IC10") (pin "2") (pinfunction "I_2") (pintype "input"))
      (node (ref "IC6") (pin "28") (pinfunction "MOSI_28") (pintype "output"))
      (node (ref "ICSP") (pin "4") (pinfunction "4_4") (pintype "passive"))
      (node (ref "JP9") (pin "5") (pinfunction "5_5") (pintype "passive"))
      (node (ref "U$2") (pin "10") (pinfunction "PB2(PDI/MOSI)_10") (pintype "bidirectional"))
    )
    (net (code "27") (name "/MOSI3") (class "Default")
      (node (ref "IC10") (pin "4") (pinfunction "O_4") (pintype "tri_state"))
      (node (ref "X2") (pin "3") (pinfunction "3-CMO_3") (pintype "bidirectional"))
    )
    (net (code "28") (name "/OSC1E") (class "Default")
      (node (ref "C9") (pin "1") (pinfunction "1_1") (pintype "passive"))
      (node (ref "IC6") (pin "76") (pinfunction "XTLP_76") (pintype "output"))
      (node (ref "Q1") (pin "2") (pinfunction "2_2") (pintype "passive"))
      (node (ref "R4") (pin "1") (pinfunction "1_1") (pintype "passive"))
    )
    (net (code "29") (name "/OSC2E") (class "Default")
      (node (ref "C12") (pin "1") (pinfunction "1_1") (pintype "passive"))
      (node (ref "IC6") (pin "75") (pinfunction "XTLN_75") (pintype "output"))
      (node (ref "Q1") (pin "1") (pinfunction "1_1") (pintype "passive"))
      (node (ref "R4") (pin "2") (pinfunction "2_2") (pintype "passive"))
    )
    (net (code "30") (name "/RESET") (class "Default")
      (node (ref "C3") (pin "1") (pinfunction "1_1") (pintype "passive"))
      (node (ref "IC1") (pin "3") (pinfunction "/MR_3") (pintype "input"))
      (node (ref "ICSP") (pin "5") (pinfunction "5_5") (pintype "passive"))
      (node (ref "R1") (pin "1") (pinfunction "1_1") (pintype "passive"))
      (node (ref "S1") (pin "P$1") (pinfunction "1_P$1") (pintype "passive"))
      (node (ref "U$2") (pin "13") (pinfunction "/RESET_13") (pintype "bidirectional"))
    )
    (net (code "31") (name "/RESET_W") (class "Default")
      (node (ref "IC1") (pin "2") (pinfunction "RES_2") (pintype "output"))
      (node (ref "IC6") (pin "59") (pinfunction "*RESET_59") (pintype "input"))
    )
    (net (code "32") (name "/RX") (class "Default")
      (node (ref "JP5") (pin "1") (pinfunction "1_1") (pintype "passive"))
      (node (ref "JP7") (pin "1") (pinfunction "1_1") (pintype "passive"))
      (node (ref "U$2") (pin "20") (pinfunction "PD2(INT2/RXD1)_20") (pintype "bidirectional"))
      (node (ref "U$3") (pin "1") (pinfunction "RO_1") (pintype "bidirectional"))
    )
    (net (code "33") (name "/RXI") (class "Default")
      (node (ref "JP2") (pin "2") (pinfunction "2_2") (pintype "passive"))
      (node (ref "XB1") (pin "3") (pinfunction "DIN/~{CONFIG}_3") (pintype "input"))
    )
    (net (code "34") (name "/RXIN") (class "Default")
      (node (ref "IC6") (pin "6") (pinfunction "RXIN_6") (pintype "input"))
      (node (ref "RN2") (pin "7") (pinfunction "2_7") (pintype "passive"))
      (node (ref "U$1") (pin "R2") (pinfunction "RD-_R2") (pintype "bidirectional"))
    )
    (net (code "35") (name "/RXIP") (class "Default")
      (node (ref "IC6") (pin "5") (pinfunction "RXIP_5") (pintype "input"))
      (node (ref "RN2") (pin "8") (pinfunction "2_8") (pintype "passive"))
      (node (ref "U$1") (pin "R1") (pinfunction "RD+_R1") (pintype "bidirectional"))
    )
    (net (code "36") (name "/RXLED") (class "Default")
      (node (ref "IC6") (pin "72") (pinfunction "RXLED_72") (pintype "output"))
      (node (ref "RX") (pin "C") (pinfunction "C_C") (pintype "passive"))
    )
    (net (code "37") (name "/SCK") (class "Default")
      (node (ref "IC11") (pin "2") (pinfunction "I_2") (pintype "input"))
      (node (ref "IC6") (pin "30") (pinfunction "SCLK_30") (pintype "input"))
      (node (ref "ICSP") (pin "3") (pinfunction "3_3") (pintype "passive"))
      (node (ref "JP9") (pin "4") (pinfunction "4_4") (pintype "passive"))
      (node (ref "U$2") (pin "9") (pinfunction "PB1(SCK)_9") (pintype "bidirectional"))
    )
    (net (code "38") (name "/SCK3") (class "Default")
      (node (ref "IC11") (pin "4") (pinfunction "O_4") (pintype "tri_state"))
      (node (ref "X2") (pin "5") (pinfunction "5-CLK_5") (pintype "bidirectional"))
    )
    (net (code "39") (name "/SCL") (class "Default")
      (node (ref "JP7") (pin "4") (pinfunction "4_4") (pintype "passive"))
      (node (ref "U$2") (pin "18") (pinfunction "PD0(INT0/OC0B/SCL)_18") (pintype "bidirectional"))
    )
    (net (code "40") (name "/SDA") (class "Default")
      (node (ref "JP7") (pin "3") (pinfunction "3_3") (pintype "passive"))
      (node (ref "U$2") (pin "19") (pinfunction "PD1(INT1/SDA)_19") (pintype "bidirectional"))
    )
    (net (code "41") (name "/SD_CS") (class "Default")
      (node (ref "IC12") (pin "2") (pinfunction "I_2") (pintype "input"))
    )
    (net (code "42") (name "/SEN") (class "Default")
      (node (ref "IC13") (pin "4") (pinfunction "O_4") (pintype "output"))
      (node (ref "IC6") (pin "31") (pinfunction "SEN_31") (pintype "input"))
    )
    (net (code "43") (name "/SEN3") (class "Default")
      (node (ref "IC12") (pin "4") (pinfunction "O_4") (pintype "tri_state"))
      (node (ref "X2") (pin "2") (pinfunction "2-CD/DAT3_2") (pintype "bidirectional"))
    )
    (net (code "44") (name "/SPDLED") (class "Default")
      (node (ref "IC6") (pin "67") (pinfunction "SPDLED_67") (pintype "output"))
      (node (ref "U$1") (pin "L2") (pinfunction "L2Y-_L2") (pintype "bidirectional"))
    )
    (net (code "45") (name "/SS") (class "Default")
      (node (ref "IC13") (pin "2") (pinfunction "I_2") (pintype "input"))
      (node (ref "IC6") (pin "29") (pinfunction "*SCS_29") (pintype "input"))
      (node (ref "JP9") (pin "3") (pinfunction "3_3") (pintype "passive"))
      (node (ref "R11") (pin "2") (pinfunction "2_2") (pintype "passive"))
      (node (ref "RXLED") (pin "A") (pinfunction "A_A") (pintype "passive"))
      (node (ref "U$2") (pin "8") (pinfunction "PB0(SS)_8") (pintype "bidirectional"))
    )
    (net (code "46") (name "/SUB_PW") (class "Default")
      (node (ref "IC4") (pin "3") (pinfunction "IN_3") (pintype "input"))
      (node (ref "JP3") (pin "2") (pinfunction "2_2") (pintype "passive"))
    )
    (net (code "47") (name "/SW") (class "Default")
      (node (ref "C10") (pin "2") (pinfunction "2_2") (pintype "passive"))
      (node (ref "D3") (pin "P$1") (pinfunction "K_P$1") (pintype "bidirectional"))
      (node (ref "IC5") (pin "6") (pinfunction "SW_6") (pintype "output"))
      (node (ref "L2") (pin "P$1") (pinfunction "1_P$1") (pintype "passive"))
    )
    (net (code "48") (name "/TX") (class "Default")
      (node (ref "JP2") (pin "1") (pinfunction "1_1") (pintype "passive"))
      (node (ref "JP7") (pin "2") (pinfunction "2_2") (pintype "passive"))
      (node (ref "U$2") (pin "21") (pinfunction "PD3(INT3/TXD1)_21") (pintype "bidirectional"))
      (node (ref "U$3") (pin "4") (pinfunction "DI_4") (pintype "bidirectional"))
    )
    (net (code "49") (name "/TXA") (class "Default")
      (node (ref "TXLED") (pin "A") (pinfunction "A_A") (pintype "passive"))
      (node (ref "U$2") (pin "22") (pinfunction "PD5(XCK/CTS)_22") (pintype "bidirectional"))
    )
    (net (code "50") (name "/TXLED") (class "Default")
      (node (ref "IC6") (pin "73") (pinfunction "TXLED_73") (pintype "output"))
      (node (ref "TX") (pin "C") (pinfunction "C_C") (pintype "passive"))
    )
    (net (code "51") (name "/TXO") (class "Default")
      (node (ref "JP5") (pin "2") (pinfunction "2_2") (pintype "passive"))
      (node (ref "R13") (pin "1") (pinfunction "1_1") (pintype "passive"))
    )
    (net (code "52") (name "/TXON") (class "Default")
      (node (ref "IC6") (pin "9") (pinfunction "TXON_9") (pintype "output"))
      (node (ref "RN2") (pin "5") (pinfunction "2_5") (pintype "passive"))
      (node (ref "U$1") (pin "R4") (pinfunction "TD-_R4") (pintype "bidirectional"))
    )
    (net (code "53") (name "/TXOP") (class "Default")
      (node (ref "IC6") (pin "8") (pinfunction "TXOP_8") (pintype "output"))
      (node (ref "RN2") (pin "6") (pinfunction "2_6") (pintype "passive"))
      (node (ref "U$1") (pin "R5") (pinfunction "TD+_R5") (pintype "bidirectional"))
    )
    (net (code "54") (name "/V1+") (class "Default")
      (node (ref "U$1") (pin "R10") (pinfunction "SPARE2_R10") (pintype "bidirectional"))
    )
    (net (code "55") (name "/V1-") (class "Default")
      (node (ref "U$1") (pin "R9") (pinfunction "SPARE1_R9") (pintype "bidirectional"))
    )
    (net (code "56") (name "/V2+") (class "Default")
      (node (ref "U$1") (pin "R7") (pinfunction "RXCT_R7") (pintype "bidirectional"))
    )
    (net (code "57") (name "/V2-") (class "Default")
      (node (ref "U$1") (pin "R8") (pinfunction "TXCT_R8") (pintype "bidirectional"))
    )
    (net (code "58") (name "/VBUS") (class "Default")
      (node (ref "F1") (pin "2") (pinfunction "2_2") (pintype "bidirectional"))
      (node (ref "JP1") (pin "1") (pinfunction "1_1") (pintype "passive"))
      (node (ref "JP3") (pin "1") (pinfunction "1_1") (pintype "passive"))
      (node (ref "U$2") (pin "2") (pinfunction "UVCC_2") (pintype "bidirectional"))
      (node (ref "U$2") (pin "7") (pinfunction "VBUS_7") (pintype "bidirectional"))
    )
    (net (code "59") (name "/VIN") (class "Default")
      (node (ref "C11") (pin "+") (pinfunction "+_+") (pintype "passive"))
      (node (ref "D1") (pin "C") (pinfunction "C_C") (pintype "passive"))
      (node (ref "JP3") (pin "3") (pinfunction "3_3") (pintype "passive"))
      (node (ref "X1") (pin "2") (pinfunction "2_2") (pintype "power_in"))
    )
    (net (code "60") (name "GND") (class "Default")
      (node (ref "C1") (pin "2") (pinfunction "2_2") (pintype "passive"))
      (node (ref "C11") (pin "-") (pinfunction "-_-") (pintype "passive"))
      (node (ref "C12") (pin "2") (pinfunction "2_2") (pintype "passive"))
      (node (ref "C13") (pin "-") (pinfunction "-_-") (pintype "passive"))
      (node (ref "C14") (pin "1") (pinfunction "1_1") (pintype "passive"))
      (node (ref "C15") (pin "2") (pinfunction "2_2") (pintype "passive"))
      (node (ref "C16") (pin "2") (pinfunction "2_2") (pintype "passive"))
      (node (ref "C17") (pin "2") (pinfunction "2_2") (pintype "passive"))
      (node (ref "C18") (pin "-") (pinfunction "-_-") (pintype "passive"))
      (node (ref "C19") (pin "-") (pinfunction "-_-") (pintype "passive"))
      (node (ref "C2") (pin "1") (pinfunction "1_1") (pintype "passive"))
      (node (ref "C20") (pin "2") (pinfunction "2_2") (pintype "passive"))
      (node (ref "C21") (pin "2") (pinfunction "2_2") (pintype "passive"))
      (node (ref "C22") (pin "2") (pinfunction "2_2") (pintype "passive"))
      (node (ref "C23") (pin "-") (pinfunction "-_-") (pintype "passive"))
      (node (ref "C24") (pin "2") (pinfunction "2_2") (pintype "passive"))
      (node (ref "C25") (pin "2") (pinfunction "2_2") (pintype "passive"))
      (node (ref "C3") (pin "2") (pinfunction "2_2") (pintype "passive"))
      (node (ref "C4") (pin "1") (pinfunction "1_1") (pintype "passive"))
      (node (ref "C5") (pin "1") (pinfunction "1_1") (pintype "passive"))
      (node (ref "C6") (pin "2") (pinfunction "2_2") (pintype "passive"))
      (node (ref "C7") (pin "2") (pinfunction "2_2") (pintype "passive"))
      (node (ref "C8") (pin "-") (pinfunction "-_-") (pintype "passive"))
      (node (ref "C9") (pin "2") (pinfunction "2_2") (pintype "passive"))
      (node (ref "D1") (pin "A") (pinfunction "A_A") (pintype "passive"))
      (node (ref "D3") (pin "P$2") (pinfunction "A_P$2") (pintype "bidirectional"))
      (node (ref "IC1") (pin "1") (pinfunction "GND_1") (pintype "power_in"))
      (node (ref "IC10") (pin "1") (pinfunction "OE_1") (pintype "input"))
      (node (ref "IC10") (pin "3") (pinfunction "GND_3") (pintype "power_in"))
      (node (ref "IC11") (pin "1") (pinfunction "OE_1") (pintype "input"))
      (node (ref "IC11") (pin "3") (pinfunction "GND_3") (pintype "power_in"))
      (node (ref "IC12") (pin "1") (pinfunction "OE_1") (pintype "input"))
      (node (ref "IC12") (pin "3") (pinfunction "GND_3") (pintype "power_in"))
      (node (ref "IC13") (pin "3") (pinfunction "GND_3") (pintype "power_in"))
      (node (ref "IC3") (pin "1") (pinfunction "OE_1") (pintype "input"))
      (node (ref "IC3") (pin "3") (pinfunction "GND_3") (pintype "power_in"))
      (node (ref "IC4") (pin "1") (pinfunction "GND/ADJ_1") (pintype "input"))
      (node (ref "IC5") (pin "2") (pinfunction "GND_2") (pintype "power_in"))
      (node (ref "IC6") (pin "10") (pinfunction "GNDA2_10") (pintype "power_in"))
      (node (ref "IC6") (pin "13") (pinfunction "GNDD1_13") (pintype "power_in"))
      (node (ref "IC6") (pin "14") (pinfunction "GNDD2_14") (pintype "power_in"))
      (node (ref "IC6") (pin "17") (pinfunction "GNDD3_17") (pintype "power_in"))
      (node (ref "IC6") (pin "19") (pinfunction "D7_19") (pintype "input"))
      (node (ref "IC6") (pin "20") (pinfunction "D6_20") (pintype "input"))
      (node (ref "IC6") (pin "21") (pinfunction "D5_21") (pintype "input"))
      (node (ref "IC6") (pin "22") (pinfunction "D4_22") (pintype "input"))
      (node (ref "IC6") (pin "23") (pinfunction "D3_23") (pintype "input"))
      (node (ref "IC6") (pin "24") (pinfunction "D2_24") (pintype "input"))
      (node (ref "IC6") (pin "25") (pinfunction "D1_25") (pintype "input"))
      (node (ref "IC6") (pin "26") (pinfunction "D0_26") (pintype "input"))
      (node (ref "IC6") (pin "32") (pinfunction "GNDD4_32") (pintype "power_in"))
      (node (ref "IC6") (pin "34") (pinfunction "TEST3_34") (pintype "input"))
      (node (ref "IC6") (pin "35") (pinfunction "TEST2_35") (pintype "input"))
      (node (ref "IC6") (pin "36") (pinfunction "TEST1_36") (pintype "input"))
      (node (ref "IC6") (pin "37") (pinfunction "TEST0_37") (pintype "input"))
      (node (ref "IC6") (pin "38") (pinfunction "A14_38") (pintype "input"))
      (node (ref "IC6") (pin "39") (pinfunction "A13_39") (pintype "input"))
      (node (ref "IC6") (pin "4") (pinfunction "GNDA1_4") (pintype "power_in"))
      (node (ref "IC6") (pin "40") (pinfunction "A12_40") (pintype "input"))
      (node (ref "IC6") (pin "41") (pinfunction "A11_41") (pintype "input"))
      (node (ref "IC6") (pin "42") (pinfunction "A10_42") (pintype "input"))
      (node (ref "IC6") (pin "43") (pinfunction "GNDD5_43") (pintype "power_in"))
      (node (ref "IC6") (pin "45") (pinfunction "A9_45") (pintype "input"))
      (node (ref "IC6") (pin "46") (pinfunction "A8_46") (pintype "input"))
      (node (ref "IC6") (pin "47") (pinfunction "A7_47") (pintype "input"))
      (node (ref "IC6") (pin "48") (pinfunction "A6_48") (pintype "input"))
      (node (ref "IC6") (pin "49") (pinfunction "A5_49") (pintype "input"))
      (node (ref "IC6") (pin "50") (pinfunction "A4_50") (pintype "input"))
      (node (ref "IC6") (pin "51") (pinfunction "A3_51") (pintype "input"))
      (node (ref "IC6") (pin "52") (pinfunction "A2_52") (pintype "input"))
      (node (ref "IC6") (pin "53") (pinfunction "A1_53") (pintype "input"))
      (node (ref "IC6") (pin "54") (pinfunction "A0_54") (pintype "input"))
      (node (ref "IC6") (pin "63") (pinfunction "OPMODE0_63") (pintype "input"))
      (node (ref "IC6") (pin "64") (pinfunction "OPMODE1_64") (pintype "input"))
      (node (ref "IC6") (pin "65") (pinfunction "OPMODE2_65") (pintype "input"))
      (node (ref "IC6") (pin "68") (pinfunction "GNDD6_68") (pintype "power_in"))
      (node (ref "IC6") (pin "77") (pinfunction "GNDA3_77") (pintype "power_in"))
      (node (ref "ICSP") (pin "6") (pinfunction "6_6") (pintype "passive"))
      (node (ref "JP4") (pin "1") (pinfunction "1_1") (pintype "passive"))
      (node (ref "ON") (pin "C") (pinfunction "C_C") (pintype "passive"))
      (node (ref "OUT1") (pin "2") (pinfunction "2_2") (pintype "bidirectional"))
      (node (ref "OUT2") (pin "2") (pinfunction "2_2") (pintype "bidirectional"))
      (node (ref "OUT3") (pin "2") (pinfunction "2_2") (pintype "bidirectional"))
      (node (ref "OUT4") (pin "2") (pinfunction "2_2") (pintype "bidirectional"))
      (node (ref "OUT5") (pin "2") (pinfunction "2_2") (pintype "bidirectional"))
      (node (ref "OUT6") (pin "2") (pinfunction "2_2") (pintype "bidirectional"))
      (node (ref "R10") (pin "1") (pinfunction "1_1") (pintype "passive"))
      (node (ref "R11") (pin "1") (pinfunction "1_1") (pintype "passive"))
      (node (ref "R14") (pin "1") (pinfunction "1_1") (pintype "passive"))
      (node (ref "R15") (pin "1") (pinfunction "1_1") (pintype "passive"))
      (node (ref "R16") (pin "1") (pinfunction "1_1") (pintype "passive"))
      (node (ref "R17") (pin "1") (pinfunction "1_1") (pintype "passive"))
      (node (ref "R2") (pin "2") (pinfunction "2_2") (pintype "passive"))
      (node (ref "R7") (pin "2") (pinfunction "2_2") (pintype "passive"))
      (node (ref "RN1") (pin "1") (pinfunction "1_1") (pintype "passive"))
      (node (ref "RN1") (pin "2") (pinfunction "1_2") (pintype "passive"))
      (node (ref "RN1") (pin "3") (pinfunction "1_3") (pintype "passive"))
      (node (ref "RN1") (pin "8") (pinfunction "2_8") (pintype "passive"))
      (node (ref "S1") (pin "P$2") (pinfunction "2_P$2") (pintype "passive"))
      (node (ref "U$1") (pin "CH1") (pinfunction "CH1_CH1") (pintype "bidirectional"))
      (node (ref "U$2") (pin "15") (pinfunction "GND_15") (pintype "bidirectional"))
      (node (ref "U$2") (pin "23") (pinfunction "GND1_23") (pintype "bidirectional"))
      (node (ref "U$2") (pin "33") (pinfunction "PE2(~{HWB})_33") (pintype "bidirectional"))
      (node (ref "U$2") (pin "35") (pinfunction "GND2_35") (pintype "bidirectional"))
      (node (ref "U$2") (pin "43") (pinfunction "GND3_43") (pintype "bidirectional"))
      (node (ref "U$2") (pin "5") (pinfunction "UGND_5") (pintype "bidirectional"))
      (node (ref "U$3") (pin "5") (pinfunction "GND_5") (pintype "bidirectional"))
      (node (ref "U1") (pin "2") (pinfunction "GND_2") (pintype "input"))
      (node (ref "X1") (pin "1") (pinfunction "1_1") (pintype "power_in"))
      (node (ref "X1") (pin "3") (pinfunction "3_3") (pintype "power_in"))
      (node (ref "X2") (pin "6") (pinfunction "6-VSS_6") (pintype "bidirectional"))
      (node (ref "X2") (pin "GND1") (pinfunction "GND_GND1") (pintype "power_in"))
      (node (ref "X2") (pin "GND2") (pinfunction "GND1_GND2") (pintype "power_in"))
      (node (ref "X2") (pin "GND3") (pinfunction "GND2_GND3") (pintype "power_in"))
      (node (ref "X2") (pin "GND4") (pinfunction "GND3_GND4") (pintype "power_in"))
      (node (ref "X3") (pin "GND") (pinfunction "GND_GND") (pintype "bidirectional"))
      (node (ref "XB1") (pin "10") (pinfunction "GND_10") (pintype "power_in"))
    )
    (net (code "61") (name "Net-(100M-PadA)") (class "Default")
      (node (ref "100M") (pin "A") (pinfunction "A_A") (pintype "passive"))
      (node (ref "R19") (pin "2") (pinfunction "2_2") (pintype "passive"))
    )
    (net (code "62") (name "Net-(ASSOC-PadC)") (class "Default")
      (node (ref "ASSOC") (pin "C") (pinfunction "C_C") (pintype "passive"))
      (node (ref "R14") (pin "2") (pinfunction "2_2") (pintype "passive"))
    )
    (net (code "63") (name "Net-(F1-Pad1)") (class "Default")
      (node (ref "F1") (pin "1") (pinfunction "1_1") (pintype "bidirectional"))
      (node (ref "X3") (pin "VBUS") (pinfunction "VBUS_VBUS") (pintype "bidirectional"))
    )
    (net (code "64") (name "Net-(FULLD-PadA)") (class "Default")
      (node (ref "FULLD") (pin "A") (pinfunction "A_A") (pintype "passive"))
      (node (ref "R18") (pin "2") (pinfunction "2_2") (pintype "passive"))
    )
    (net (code "65") (name "Net-(IC3A-O)") (class "Default")
      (node (ref "IC3") (pin "4") (pinfunction "O_4") (pintype "tri_state"))
      (node (ref "L") (pin "A") (pinfunction "A_A") (pintype "passive"))
    )
    (net (code "66") (name "Net-(IC6-*CS)") (class "Default")
      (node (ref "IC6") (pin "55") (pinfunction "*CS_55") (pintype "input"))
      (node (ref "IC6") (pin "57") (pinfunction "*WR_57") (pintype "input"))
      (node (ref "IC6") (pin "58") (pinfunction "*RD_58") (pintype "input"))
      (node (ref "R12") (pin "1") (pinfunction "1_1") (pintype "passive"))
    )
    (net (code "67") (name "Net-(IC6-RSET-BG)") (class "Default")
      (node (ref "IC6") (pin "1") (pinfunction "RSET-BG_1") (pintype "input"))
      (node (ref "R3") (pin "1") (pinfunction "1_1") (pintype "passive"))
    )
    (net (code "68") (name "Net-(LED13-PadC)") (class "Default")
      (node (ref "LED13") (pin "C") (pinfunction "C_C") (pintype "passive"))
      (node (ref "R17") (pin "2") (pinfunction "2_2") (pintype "passive"))
    )
    (net (code "69") (name "Net-(R2-Pad1)") (class "Default")
      (node (ref "R2") (pin "1") (pinfunction "1_1") (pintype "passive"))
      (node (ref "R3") (pin "2") (pinfunction "2_2") (pintype "passive"))
    )
    (net (code "70") (name "Net-(R8-Pad1)") (class "Default")
      (node (ref "R8") (pin "1") (pinfunction "1_1") (pintype "passive"))
      (node (ref "X3") (pin "D-") (pinfunction "D-_D-") (pintype "bidirectional"))
    )
    (net (code "71") (name "Net-(R9-Pad1)") (class "Default")
      (node (ref "R9") (pin "1") (pinfunction "1_1") (pintype "passive"))
      (node (ref "X3") (pin "D+") (pinfunction "D+_D+") (pintype "bidirectional"))
    )
    (net (code "72") (name "Net-(R10-Pad2)") (class "Default")
      (node (ref "R10") (pin "2") (pinfunction "2_2") (pintype "passive"))
      (node (ref "WIRELESS_ON") (pin "C") (pinfunction "C_C") (pintype "passive"))
    )
    (net (code "73") (name "Net-(R15-Pad2)") (class "Default")
      (node (ref "R15") (pin "2") (pinfunction "2_2") (pintype "passive"))
      (node (ref "TXLED") (pin "C") (pinfunction "C_C") (pintype "passive"))
    )
    (net (code "74") (name "Net-(R16-Pad2)") (class "Default")
      (node (ref "R16") (pin "2") (pinfunction "2_2") (pintype "passive"))
      (node (ref "RXLED") (pin "C") (pinfunction "C_C") (pintype "passive"))
    )
    (net (code "75") (name "Net-(RN1B-2)") (class "Default")
      (node (ref "L") (pin "C") (pinfunction "C_C") (pintype "passive"))
      (node (ref "RN1") (pin "6") (pinfunction "2_6") (pintype "passive"))
      (node (ref "RN1") (pin "7") (pinfunction "2_7") (pintype "passive"))
    )
    (net (code "76") (name "Net-(RN1D-2)") (class "Default")
      (node (ref "ON") (pin "A") (pinfunction "A_A") (pintype "passive"))
      (node (ref "RN1") (pin "5") (pinfunction "2_5") (pintype "passive"))
    )
    (net (code "77") (name "Net-(RN2B-1)") (class "Default")
      (node (ref "C4") (pin "2") (pinfunction "2_2") (pintype "passive"))
      (node (ref "RN2") (pin "1") (pinfunction "1_1") (pintype "passive"))
      (node (ref "RN2") (pin "2") (pinfunction "1_2") (pintype "passive"))
    )
    (net (code "78") (name "Net-(RN2C-1)") (class "Default")
      (node (ref "C2") (pin "2") (pinfunction "2_2") (pintype "passive"))
      (node (ref "RN2") (pin "3") (pinfunction "1_3") (pintype "passive"))
      (node (ref "RN2") (pin "4") (pinfunction "1_4") (pintype "passive"))
    )
    (net (code "79") (name "Net-(RN3A-2)") (class "Default")
      (node (ref "RN3") (pin "8") (pinfunction "2_8") (pintype "passive"))
      (node (ref "TX") (pin "A") (pinfunction "A_A") (pintype "passive"))
    )
    (net (code "80") (name "Net-(RN3B-2)") (class "Default")
      (node (ref "RN3") (pin "7") (pinfunction "2_7") (pintype "passive"))
      (node (ref "RX") (pin "A") (pinfunction "A_A") (pintype "passive"))
    )
    (net (code "81") (name "Net-(RN3C-2)") (class "Default")
      (node (ref "RN3") (pin "6") (pinfunction "2_6") (pintype "passive"))
      (node (ref "U$1") (pin "L1") (pinfunction "L1Y+_L1") (pintype "bidirectional"))
    )
    (net (code "82") (name "Net-(RN3D-2)") (class "Default")
      (node (ref "RN3") (pin "5") (pinfunction "2_5") (pintype "passive"))
      (node (ref "U$1") (pin "L3") (pinfunction "L3G+_L3") (pintype "bidirectional"))
    )
    (net (code "83") (name "Net-(U$2-AVCC)") (class "Default")
      (node (ref "JP1") (pin "2") (pinfunction "2_2") (pintype "passive"))
      (node (ref "U$2") (pin "14") (pinfunction "VCC_14") (pintype "bidirectional"))
      (node (ref "U$2") (pin "24") (pinfunction "AVCC_24") (pintype "bidirectional"))
      (node (ref "U$2") (pin "34") (pinfunction "VCC1_34") (pintype "bidirectional"))
      (node (ref "U$2") (pin "44") (pinfunction "AVCC1_44") (pintype "bidirectional"))
    )
    (net (code "84") (name "Net-(U$2-D+)") (class "Default")
      (node (ref "R9") (pin "2") (pinfunction "2_2") (pintype "passive"))
      (node (ref "U$2") (pin "4") (pinfunction "D+_4") (pintype "bidirectional"))
    )
    (net (code "85") (name "Net-(U$2-D-)") (class "Default")
      (node (ref "R8") (pin "2") (pinfunction "2_2") (pintype "passive"))
      (node (ref "U$2") (pin "3") (pinfunction "D-_3") (pintype "bidirectional"))
    )
    (net (code "86") (name "Net-(U$2-PF0(ADC0))") (class "Default")
      (node (ref "JP6") (pin "1") (pinfunction "1_1") (pintype "passive"))
      (node (ref "U$2") (pin "41") (pinfunction "PF0(ADC0)_41") (pintype "bidirectional"))
    )
    (net (code "87") (name "Net-(U$2-PF1(ADC1))") (class "Default")
      (node (ref "JP6") (pin "2") (pinfunction "2_2") (pintype "passive"))
      (node (ref "U$2") (pin "40") (pinfunction "PF1(ADC1)_40") (pintype "bidirectional"))
    )
    (net (code "88") (name "Net-(U$2-PF4(ADC4{slash}TCK))") (class "Default")
      (node (ref "JP6") (pin "3") (pinfunction "3_3") (pintype "passive"))
      (node (ref "U$2") (pin "39") (pinfunction "PF4(ADC4/TCK)_39") (pintype "bidirectional"))
    )
    (net (code "89") (name "Net-(U$2-PF5(ADC5{slash}TMS))") (class "Default")
      (node (ref "JP6") (pin "4") (pinfunction "4_4") (pintype "passive"))
      (node (ref "U$2") (pin "38") (pinfunction "PF5(ADC5/TMS)_38") (pintype "bidirectional"))
    )
    (net (code "90") (name "Net-(U$2-PF6(ADC6{slash}TDO))") (class "Default")
      (node (ref "JP6") (pin "5") (pinfunction "5_5") (pintype "passive"))
      (node (ref "U$2") (pin "37") (pinfunction "PF6(ADC6/TDO)_37") (pintype "bidirectional"))
    )
    (net (code "91") (name "Net-(U$2-PF7(ADC7(TDI))") (class "Default")
      (node (ref "JP6") (pin "6") (pinfunction "6_6") (pintype "passive"))
      (node (ref "U$2") (pin "36") (pinfunction "PF7(ADC7(TDI)_36") (pintype "bidirectional"))
    )
    (net (code "92") (name "Net-(U$2-UCAP)") (class "Default")
      (node (ref "C15") (pin "1") (pinfunction "1_1") (pintype "passive"))
      (node (ref "U$2") (pin "6") (pinfunction "UCAP_6") (pintype "bidirectional"))
    )
    (net (code "93") (name "Net-(U$2-XTAL1)") (class "Default")
      (node (ref "C14") (pin "2") (pinfunction "2_2") (pintype "passive"))
      (node (ref "U$2") (pin "17") (pinfunction "XTAL1_17") (pintype "bidirectional"))
      (node (ref "Y1") (pin "3") (pinfunction "2_3") (pintype "passive"))
    )
    (net (code "94") (name "Net-(U$2-XTAL2)") (class "Default")
      (node (ref "C5") (pin "2") (pinfunction "2_2") (pintype "passive"))
      (node (ref "U$2") (pin "16") (pinfunction "XTAL2_16") (pintype "bidirectional"))
      (node (ref "Y1") (pin "1") (pinfunction "1_1") (pintype "passive"))
    )
    (net (code "95") (name "Net-(U$3-DE)") (class "Default")
      (node (ref "JP4") (pin "2") (pinfunction "2_2") (pintype "passive"))
      (node (ref "U$3") (pin "2") (pinfunction "/RE_2") (pintype "bidirectional"))
      (node (ref "U$3") (pin "3") (pinfunction "DE_3") (pintype "bidirectional"))
    )
    (net (code "96") (name "Net-(XB1-ASSOC{slash}AD5{slash}DIO5)") (class "Default")
      (node (ref "ASSOC") (pin "A") (pinfunction "A_A") (pintype "passive"))
      (node (ref "XB1") (pin "15") (pinfunction "ASSOC/AD5/DIO5_15") (pintype "bidirectional"))
    )
    (net (code "97") (name "Net-(XB1-DOUT)") (class "Default")
      (node (ref "R13") (pin "2") (pinfunction "2_2") (pintype "passive"))
      (node (ref "XB1") (pin "2") (pinfunction "DOUT_2") (pintype "output"))
    )
    (net (code "98") (name "Net-(XB1-ON{slash}~{SLEEP})") (class "Default")
      (node (ref "WIRELESS_ON") (pin "A") (pinfunction "A_A") (pintype "passive"))
      (node (ref "XB1") (pin "13") (pinfunction "ON/~{SLEEP}_13") (pintype "output"))
    )
    (net (code "99") (name "unconnected-(IC3A-I-Pad2)") (class "Default")
      (node (ref "IC3") (pin "2") (pinfunction "I_2") (pintype "input"))
    )
    (net (code "100") (name "unconnected-(IC6-NC-Pad3)") (class "Default")
      (node (ref "IC6") (pin "3") (pinfunction "NC_3") (pintype "no_connect"))
    )
    (net (code "101") (name "unconnected-(IC6-NC1-Pad60)") (class "Default")
      (node (ref "IC6") (pin "60") (pinfunction "NC1_60") (pintype "no_connect"))
    )
    (net (code "102") (name "unconnected-(IC6-NC2-Pad61)") (class "Default")
      (node (ref "IC6") (pin "61") (pinfunction "NC2_61") (pintype "no_connect"))
    )
    (net (code "103") (name "unconnected-(IC6-NC3-Pad62)") (class "Default")
      (node (ref "IC6") (pin "62") (pinfunction "NC3_62") (pintype "no_connect"))
    )
    (net (code "104") (name "unconnected-(IC6-NC4-Pad78)") (class "Default")
      (node (ref "IC6") (pin "78") (pinfunction "NC4_78") (pintype "no_connect"))
    )
    (net (code "105") (name "unconnected-(IC6-NC5-Pad79)") (class "Default")
      (node (ref "IC6") (pin "79") (pinfunction "NC5_79") (pintype "no_connect"))
    )
    (net (code "106") (name "unconnected-(IC6-NC6-Pad80)") (class "Default")
      (node (ref "IC6") (pin "80") (pinfunction "NC6_80") (pintype "no_connect"))
    )
    (net (code "107") (name "unconnected-(JP1-Pad3)") (class "Default")
      (node (ref "JP1") (pin "3") (pinfunction "3_3") (pintype "passive"))
    )
    (net (code "108") (name "unconnected-(JP10-1-PadP$1)") (class "Default")
      (node (ref "JP10") (pin "P$1") (pinfunction "1_P$1") (pintype "passive"))
    )
    (net (code "109") (name "unconnected-(JP12-1-PadP$1)") (class "Default")
      (node (ref "JP12") (pin "P$1") (pinfunction "1_P$1") (pintype "passive"))
    )
    (net (code "110") (name "unconnected-(JP13-1-PadP$1)") (class "Default")
      (node (ref "JP13") (pin "P$1") (pinfunction "1_P$1") (pintype "passive"))
    )
    (net (code "111") (name "unconnected-(OUT1-Pad1)") (class "Default")
      (node (ref "OUT1") (pin "1") (pinfunction "1_1") (pintype "bidirectional"))
    )
    (net (code "112") (name "unconnected-(OUT1-Pad3)") (class "Default")
      (node (ref "OUT1") (pin "3") (pinfunction "3_3") (pintype "bidirectional"))
    )
    (net (code "113") (name "unconnected-(OUT1-Pad5)") (class "Default")
      (node (ref "OUT1") (pin "5") (pinfunction "5_5") (pintype "bidirectional"))
    )
    (net (code "114") (name "unconnected-(OUT1-Pad7)") (class "Default")
      (node (ref "OUT1") (pin "7") (pinfunction "7_7") (pintype "bidirectional"))
    )
    (net (code "115") (name "unconnected-(OUT1-Pad8)") (class "Default")
      (node (ref "OUT1") (pin "8") (pinfunction "8_8") (pintype "bidirectional"))
    )
    (net (code "116") (name "unconnected-(OUT2-Pad1)") (class "Default")
      (node (ref "OUT2") (pin "1") (pinfunction "1_1") (pintype "bidirectional"))
    )
    (net (code "117") (name "unconnected-(OUT2-Pad3)") (class "Default")
      (node (ref "OUT2") (pin "3") (pinfunction "3_3") (pintype "bidirectional"))
    )
    (net (code "118") (name "unconnected-(OUT2-Pad5)") (class "Default")
      (node (ref "OUT2") (pin "5") (pinfunction "5_5") (pintype "bidirectional"))
    )
    (net (code "119") (name "unconnected-(OUT2-Pad7)") (class "Default")
      (node (ref "OUT2") (pin "7") (pinfunction "7_7") (pintype "bidirectional"))
    )
    (net (code "120") (name "unconnected-(OUT2-Pad8)") (class "Default")
      (node (ref "OUT2") (pin "8") (pinfunction "8_8") (pintype "bidirectional"))
    )
    (net (code "121") (name "unconnected-(OUT3-Pad1)") (class "Default")
      (node (ref "OUT3") (pin "1") (pinfunction "1_1") (pintype "bidirectional"))
    )
    (net (code "122") (name "unconnected-(OUT3-Pad3)") (class "Default")
      (node (ref "OUT3") (pin "3") (pinfunction "3_3") (pintype "bidirectional"))
    )
    (net (code "123") (name "unconnected-(OUT3-Pad5)") (class "Default")
      (node (ref "OUT3") (pin "5") (pinfunction "5_5") (pintype "bidirectional"))
    )
    (net (code "124") (name "unconnected-(OUT3-Pad7)") (class "Default")
      (node (ref "OUT3") (pin "7") (pinfunction "7_7") (pintype "bidirectional"))
    )
    (net (code "125") (name "unconnected-(OUT3-Pad8)") (class "Default")
      (node (ref "OUT3") (pin "8") (pinfunction "8_8") (pintype "bidirectional"))
    )
    (net (code "126") (name "unconnected-(OUT4-Pad1)") (class "Default")
      (node (ref "OUT4") (pin "1") (pinfunction "1_1") (pintype "bidirectional"))
    )
    (net (code "127") (name "unconnected-(OUT4-Pad3)") (class "Default")
      (node (ref "OUT4") (pin "3") (pinfunction "3_3") (pintype "bidirectional"))
    )
    (net (code "128") (name "unconnected-(OUT4-Pad5)") (class "Default")
      (node (ref "OUT4") (pin "5") (pinfunction "5_5") (pintype "bidirectional"))
    )
    (net (code "129") (name "unconnected-(OUT4-Pad7)") (class "Default")
      (node (ref "OUT4") (pin "7") (pinfunction "7_7") (pintype "bidirectional"))
    )
    (net (code "130") (name "unconnected-(OUT4-Pad8)") (class "Default")
      (node (ref "OUT4") (pin "8") (pinfunction "8_8") (pintype "bidirectional"))
    )
    (net (code "131") (name "unconnected-(OUT5-Pad1)") (class "Default")
      (node (ref "OUT5") (pin "1") (pinfunction "1_1") (pintype "bidirectional"))
    )
    (net (code "132") (name "unconnected-(OUT5-Pad3)") (class "Default")
      (node (ref "OUT5") (pin "3") (pinfunction "3_3") (pintype "bidirectional"))
    )
    (net (code "133") (name "unconnected-(OUT5-Pad5)") (class "Default")
      (node (ref "OUT5") (pin "5") (pinfunction "5_5") (pintype "bidirectional"))
    )
    (net (code "134") (name "unconnected-(OUT5-Pad7)") (class "Default")
      (node (ref "OUT5") (pin "7") (pinfunction "7_7") (pintype "bidirectional"))
    )
    (net (code "135") (name "unconnected-(OUT5-Pad8)") (class "Default")
      (node (ref "OUT5") (pin "8") (pinfunction "8_8") (pintype "bidirectional"))
    )
    (net (code "136") (name "unconnected-(OUT6-Pad1)") (class "Default")
      (node (ref "OUT6") (pin "1") (pinfunction "1_1") (pintype "bidirectional"))
    )
    (net (code "137") (name "unconnected-(OUT6-Pad3)") (class "Default")
      (node (ref "OUT6") (pin "3") (pinfunction "3_3") (pintype "bidirectional"))
    )
    (net (code "138") (name "unconnected-(OUT6-Pad5)") (class "Default")
      (node (ref "OUT6") (pin "5") (pinfunction "5_5") (pintype "bidirectional"))
    )
    (net (code "139") (name "unconnected-(OUT6-Pad7)") (class "Default")
      (node (ref "OUT6") (pin "7") (pinfunction "7_7") (pintype "bidirectional"))
    )
    (net (code "140") (name "unconnected-(OUT6-Pad8)") (class "Default")
      (node (ref "OUT6") (pin "8") (pinfunction "8_8") (pintype "bidirectional"))
    )
    (net (code "141") (name "unconnected-(U$1-NC-PadR6)") (class "Default")
      (node (ref "U$1") (pin "R6") (pinfunction "NC_R6") (pintype "bidirectional"))
    )
    (net (code "142") (name "unconnected-(U$1-PadCH2)") (class "Default")
      (node (ref "U$1") (pin "CH2") (pinfunction "CH2_CH2") (pintype "bidirectional"))
    )
    (net (code "143") (name "unconnected-(U$2-AREF-Pad42)") (class "Default")
      (node (ref "U$2") (pin "42") (pinfunction "AREF_42") (pintype "bidirectional"))
    )
    (net (code "144") (name "unconnected-(U1-BP-Pad4)") (class "Default")
      (node (ref "U1") (pin "4") (pinfunction "BP_4") (pintype "input"))
    )
    (net (code "145") (name "unconnected-(X2-1-DAT2-Pad1)") (class "Default")
      (node (ref "X2") (pin "1") (pinfunction "1-DAT2_1") (pintype "bidirectional"))
    )
    (net (code "146") (name "unconnected-(X2-8-DAT1-Pad8)") (class "Default")
      (node (ref "X2") (pin "8") (pinfunction "8-DAT1_8") (pintype "bidirectional"))
    )
    (net (code "147") (name "unconnected-(XB1-AD0{slash}DIO0-Pad20)") (class "Default")
      (node (ref "XB1") (pin "20") (pinfunction "AD0/DIO0_20") (pintype "bidirectional"))
    )
    (net (code "148") (name "unconnected-(XB1-AD1{slash}DIO1-Pad19)") (class "Default")
      (node (ref "XB1") (pin "19") (pinfunction "AD1/DIO1_19") (pintype "bidirectional"))
    )
    (net (code "149") (name "unconnected-(XB1-AD2{slash}DIO2-Pad18)") (class "Default")
      (node (ref "XB1") (pin "18") (pinfunction "AD2/DIO2_18") (pintype "bidirectional"))
    )
    (net (code "150") (name "unconnected-(XB1-CD{slash}DOUT_EN{slash}DO8-Pad4)") (class "Default")
      (node (ref "XB1") (pin "4") (pinfunction "CD/DOUT_EN/DO8_4") (pintype "output"))
    )
    (net (code "151") (name "unconnected-(XB1-COORD_SEL{slash}AD3{slash}DIO3-Pad17)") (class "Default")
      (node (ref "XB1") (pin "17") (pinfunction "COORD_SEL/AD3/DIO3_17") (pintype "bidirectional"))
    )
    (net (code "152") (name "unconnected-(XB1-PWM0{slash}RSSI-Pad6)") (class "Default")
      (node (ref "XB1") (pin "6") (pinfunction "PWM0/RSSI_6") (pintype "output"))
    )
    (net (code "153") (name "unconnected-(XB1-RF_TX{slash}AD4{slash}DIO4-Pad11)") (class "Default")
      (node (ref "XB1") (pin "11") (pinfunction "RF_TX/AD4/DIO4_11") (pintype "bidirectional"))
    )
    (net (code "154") (name "unconnected-(XB1-VREF-Pad14)") (class "Default")
      (node (ref "XB1") (pin "14") (pinfunction "VREF_14") (pintype "input"))
    )
    (net (code "155") (name "unconnected-(XB1-~{CTS}{slash}DIO7-Pad12)") (class "Default")
      (node (ref "XB1") (pin "12") (pinfunction "~{CTS}/DIO7_12") (pintype "bidirectional"))
    )
    (net (code "156") (name "unconnected-(XB1-~{DTR}{slash}SLEEP_RQ{slash}DI8-Pad9)") (class "Default")
      (node (ref "XB1") (pin "9") (pinfunction "~{DTR}/SLEEP_RQ/DI8_9") (pintype "bidirectional"))
    )
    (net (code "157") (name "unconnected-(XB1-~{RESET}-Pad5)") (class "Default")
      (node (ref "XB1") (pin "5") (pinfunction "~{RESET}_5") (pintype "input"))
    )
    (net (code "158") (name "unconnected-(XB1-~{RTS}{slash}AD6{slash}DIO6-Pad16)") (class "Default")
      (node (ref "XB1") (pin "16") (pinfunction "~{RTS}/AD6/DIO6_16") (pintype "bidirectional"))
    )
  )
)
